# Sheet1.net
KiCad netlist of a schematic drawn in Altium Designer
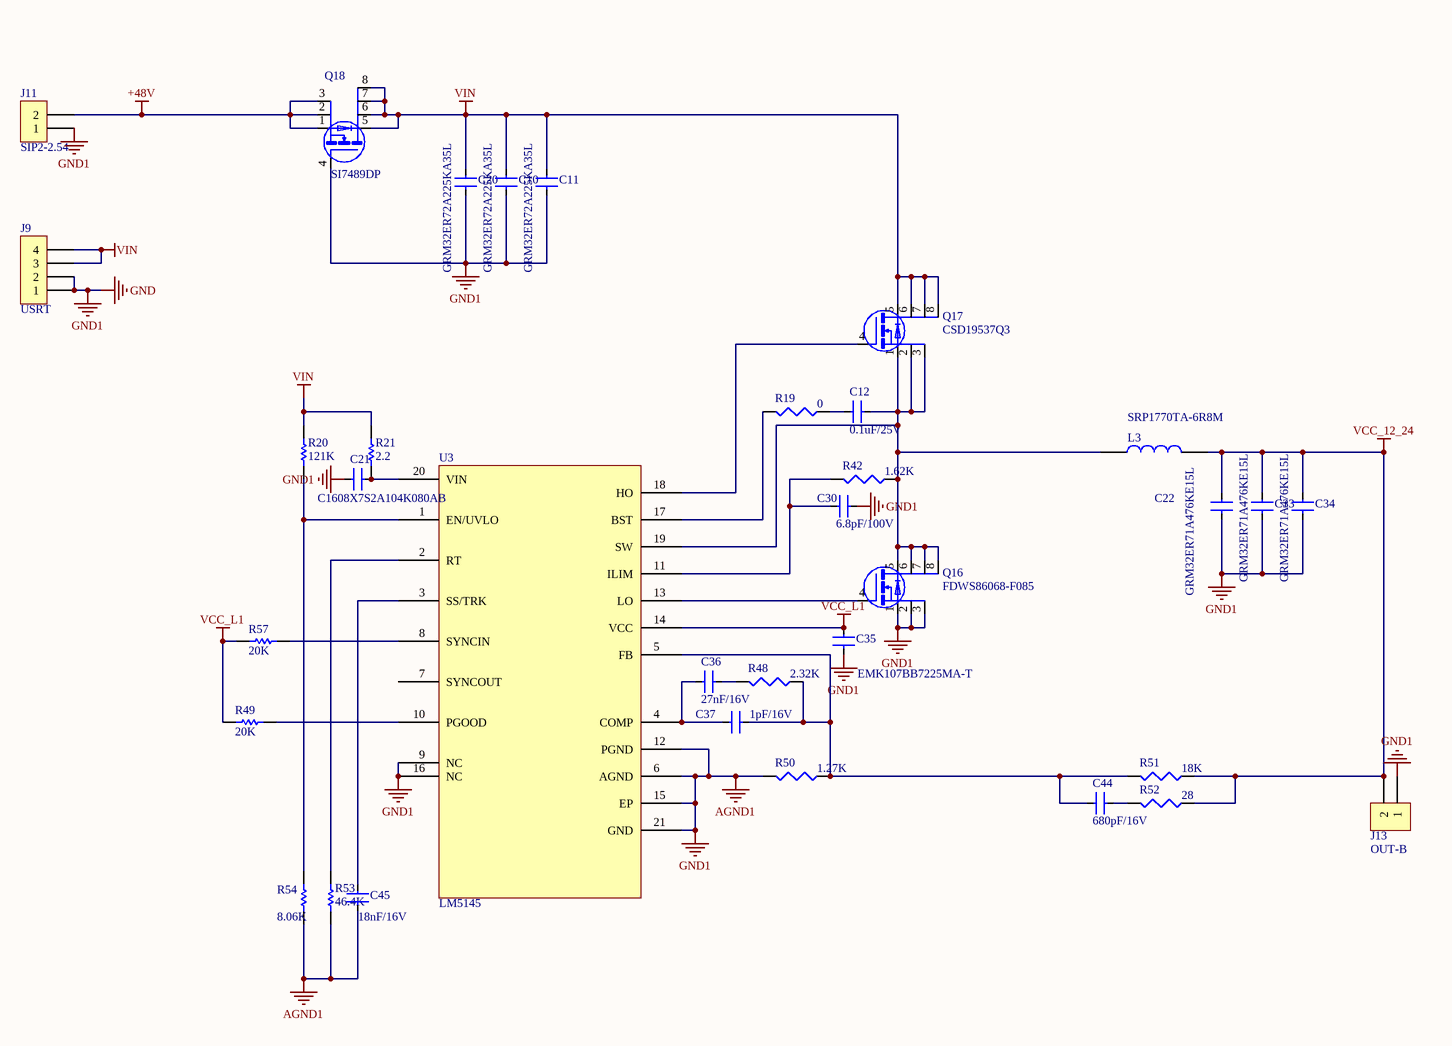
[diagram p0: Sheet1.SchDoc]

(export (version "E")
  (design (tool "Eeschema 10.0.6"))
  (components
    (comp (ref "C10")
      (value "GRM32ER72A225KA35L")
      (footprint "1210C")
      (description "CCX85-103")
      (libsource (lib "无极性电容") (part "0.01UF"))
    )
    (comp (ref "C11")
      (value "GRM32ER72A225KA35L")
      (footprint "1210C")
      (description "CCX85-103")
      (libsource (lib "无极性电容") (part "0.01UF"))
    )
    (comp (ref "C12")
      (value "0.1uF/25V")
      (footprint "0603C")
      (description "CCX85-103")
      (libsource (lib "无极性电容") (part "0.01UF"))
    )
    (comp (ref "C20")
      (value "GRM32ER72A225KA35L")
      (footprint "1210C")
      (description "CCX85-103")
      (libsource (lib "无极性电容") (part "0.01UF"))
    )
    (comp (ref "C21")
      (value "C1608X7S2A104K080AB")
      (footprint "0603C")
      (description "CCX85-103")
      (libsource (lib "无极性电容") (part "0.01UF"))
    )
    (comp (ref "C22")
      (value "GRM32ER71A476KE15L")
      (footprint "1210C")
      (description "CCX85-103")
      (libsource (lib "无极性电容") (part "0.01UF"))
    )
    (comp (ref "C30")
      (value "6.8pF/100V")
      (footprint "0603C")
      (description "CCX85-103")
      (libsource (lib "无极性电容") (part "0.01UF"))
    )
    (comp (ref "C33")
      (value "GRM32ER71A476KE15L")
      (footprint "1210C")
      (description "CCX85-103")
      (libsource (lib "无极性电容") (part "0.01UF"))
    )
    (comp (ref "C34")
      (value "GRM32ER71A476KE15L")
      (footprint "1210C")
      (description "CCX85-103")
      (libsource (lib "无极性电容") (part "0.01UF"))
    )
    (comp (ref "C35")
      (value "EMK107BB7225MA-T")
      (footprint "0603C")
      (description "CCX85-103")
      (libsource (lib "无极性电容") (part "0.01UF"))
    )
    (comp (ref "C36")
      (value "27nF/16V")
      (footprint "0603C")
      (description "CCX85-103")
      (libsource (lib "无极性电容") (part "0.01UF"))
    )
    (comp (ref "C37")
      (value "1pF/16V")
      (footprint "0603C")
      (description "CCX85-103")
      (libsource (lib "无极性电容") (part "0.01UF"))
    )
    (comp (ref "C44")
      (value "680pF/16V")
      (footprint "0603C")
      (description "CCX85-103")
      (libsource (lib "无极性电容") (part "0.01UF"))
    )
    (comp (ref "C45")
      (value "18nF/16V")
      (footprint "0603C")
      (description "CCX85-103")
      (libsource (lib "无极性电容") (part "0.01UF"))
    )
    (comp (ref "J9")
      (value "USRT")
      (footprint "SIP-4L")
      (description "CN-SIP4-2.54")
      (libsource (lib "接插件") (part "SIP4-2.54"))
    )
    (comp (ref "J11")
      (value "SIP2-2.54")
      (footprint "CH3.96-2P")
      (description "CN-SIP2-2.54")
      (libsource (lib "接插件") (part "SIP2-2.54"))
    )
    (comp (ref "J13")
      (value "OUT-B")
      (footprint "CH3.96-2P")
      (description "Connector")
      (libsource (lib "SM") (part "CON2"))
    )
    (comp (ref "L3")
      (value "SRP1770TA-6R8M")
      (footprint "SRP1270-2R2M")
      (libsource (lib "*") (part "INDUCTOR"))
    )
    (comp (ref "Q16")
      (value "FDWS86068-F085")
      (footprint "PowerPAK SO-8")
      (description "Si4004DY")
      (libsource (lib "Schlib_20110825") (part "Si4004DY"))
    )
    (comp (ref "Q17")
      (value "CSD19537Q3")
      (footprint "PowerPAK SO-8")
      (description "Si4004DY")
      (libsource (lib "Schlib_20110825") (part "Si4004DY"))
    )
    (comp (ref "Q18")
      (value "SI7489DP")
      (footprint "PowerPAK SO-8")
      (description "Si4004DY")
      (libsource (lib "") (part "Si4004DY_1"))
    )
    (comp (ref "R19")
      (value "0")
      (footprint "0603R")
      (description "Resistor")
      (fields (field (name "PUBLISHER") "Altium Limited"))
      (libsource (lib "SM") (part "Res3"))
    )
    (comp (ref "R20")
      (value "121K")
      (footprint "0805R")
      (description "Semiconductor Resistor")
      (fields (field (name "PUBLISHER") "Altium Limited"))
      (libsource (lib "Miscellaneous Devices") (part "Res Semi"))
    )
    (comp (ref "R21")
      (value "2.2")
      (footprint "0603R")
      (description "Semiconductor Resistor")
      (fields (field (name "PUBLISHER") "Altium Limited"))
      (libsource (lib "Miscellaneous Devices") (part "Res Semi"))
    )
    (comp (ref "R42")
      (value "1.62K")
      (footprint "0603R")
      (description "Resistor")
      (fields (field (name "PUBLISHER") "Altium Limited"))
      (libsource (lib "SM") (part "Res3"))
    )
    (comp (ref "R48")
      (value "2.32K")
      (footprint "0603R")
      (description "Resistor")
      (fields (field (name "PUBLISHER") "Altium Limited"))
      (libsource (lib "SM") (part "Res3"))
    )
    (comp (ref "R49")
      (value "20K")
      (footprint "0603R")
      (description "Semiconductor Resistor")
      (fields (field (name "PUBLISHER") "Altium Limited"))
      (libsource (lib "Miscellaneous Devices") (part "Res Semi"))
    )
    (comp (ref "R50")
      (value "1.27K")
      (footprint "0603R")
      (description "Resistor")
      (fields (field (name "PUBLISHER") "Altium Limited"))
      (libsource (lib "SM") (part "Res3"))
    )
    (comp (ref "R51")
      (value "18K")
      (footprint "0603R")
      (description "Resistor")
      (fields (field (name "PUBLISHER") "Altium Limited"))
      (libsource (lib "SM") (part "Res3"))
    )
    (comp (ref "R52")
      (value "28")
      (footprint "0603R")
      (description "Resistor")
      (fields (field (name "PUBLISHER") "Altium Limited"))
      (libsource (lib "SM") (part "Res3"))
    )
    (comp (ref "R53")
      (value "46.4K")
      (footprint "0603R")
      (description "Semiconductor Resistor")
      (fields (field (name "PUBLISHER") "Altium Limited"))
      (libsource (lib "Miscellaneous Devices") (part "Res Semi"))
    )
    (comp (ref "R54")
      (value "8.06K")
      (footprint "0603R")
      (description "Semiconductor Resistor")
      (fields (field (name "PUBLISHER") "Altium Limited"))
      (libsource (lib "Miscellaneous Devices") (part "Res Semi"))
    )
    (comp (ref "R57")
      (value "20K")
      (footprint "0603R")
      (description "Semiconductor Resistor")
      (fields (field (name "PUBLISHER") "Altium Limited"))
      (libsource (lib "Miscellaneous Devices") (part "Res Semi"))
    )
    (comp (ref "U3")
      (value "LM5145")
      (footprint "QFN050P600-8N")
      (libsource (lib "Schlib_20110825") (part "LM5145"))
    )
  )
  (nets
    (net (code "1") (name "+48V") (class "Default")
      (node (ref "J11") (pin "2") (pinfunction "2_2") (pintype "passive"))
      (node (ref "Q18") (pin "1") (pinfunction "S_1") (pintype "passive"))
      (node (ref "Q18") (pin "2") (pinfunction "S_2") (pintype "passive"))
      (node (ref "Q18") (pin "3") (pinfunction "S_3") (pintype "passive"))
    )
    (net (code "2") (name "AGND1") (class "Default")
      (node (ref "C10") (pin "2") (pinfunction "2_2") (pintype "passive"))
      (node (ref "C11") (pin "2") (pinfunction "2_2") (pintype "passive"))
      (node (ref "C20") (pin "2") (pinfunction "2_2") (pintype "passive"))
      (node (ref "C21") (pin "1") (pinfunction "1_1") (pintype "passive"))
      (node (ref "C22") (pin "2") (pinfunction "2_2") (pintype "passive"))
      (node (ref "C30") (pin "1") (pinfunction "1_1") (pintype "passive"))
      (node (ref "C33") (pin "2") (pinfunction "2_2") (pintype "passive"))
      (node (ref "C34") (pin "2") (pinfunction "2_2") (pintype "passive"))
      (node (ref "C35") (pin "2") (pinfunction "2_2") (pintype "passive"))
      (node (ref "C45") (pin "2") (pinfunction "2_2") (pintype "passive"))
      (node (ref "J11") (pin "1") (pinfunction "1_1") (pintype "passive"))
      (node (ref "J13") (pin "1") (pinfunction "1_1") (pintype "passive"))
      (node (ref "J9") (pin "1") (pinfunction "1_1") (pintype "passive"))
      (node (ref "J9") (pin "2") (pinfunction "2_2") (pintype "passive"))
      (node (ref "Q16") (pin "1") (pinfunction "S_1") (pintype "passive"))
      (node (ref "Q16") (pin "2") (pinfunction "S_2") (pintype "passive"))
      (node (ref "Q16") (pin "3") (pinfunction "S_3") (pintype "passive"))
      (node (ref "Q18") (pin "4") (pinfunction "G_4") (pintype "passive"))
      (node (ref "R50") (pin "2") (pinfunction "2_2") (pintype "passive"))
      (node (ref "R53") (pin "1") (pinfunction "1_1") (pintype "passive"))
      (node (ref "R54") (pin "1") (pinfunction "1_1") (pintype "passive"))
      (node (ref "U3") (pin "12") (pinfunction "PGND_12") (pintype "passive"))
      (node (ref "U3") (pin "15") (pinfunction "EP_15") (pintype "passive"))
      (node (ref "U3") (pin "16") (pinfunction "NC_16") (pintype "passive"))
      (node (ref "U3") (pin "21") (pinfunction "GND_21") (pintype "passive"))
      (node (ref "U3") (pin "6") (pinfunction "AGND_6") (pintype "passive"))
      (node (ref "U3") (pin "9") (pinfunction "NC_9") (pintype "passive"))
    )
    (net (code "3") (name "Net-(C12-Pad1)") (class "Default")
      (node (ref "C12") (pin "1") (pinfunction "1_1") (pintype "passive"))
      (node (ref "R19") (pin "1") (pinfunction "1_1") (pintype "passive"))
    )
    (net (code "4") (name "Net-(C36-Pad2)") (class "Default")
      (node (ref "C36") (pin "2") (pinfunction "2_2") (pintype "passive"))
      (node (ref "R48") (pin "2") (pinfunction "2_2") (pintype "passive"))
    )
    (net (code "5") (name "Net-(C44-Pad2)") (class "Default")
      (node (ref "C44") (pin "2") (pinfunction "2_2") (pintype "passive"))
      (node (ref "R52") (pin "2") (pinfunction "2_2") (pintype "passive"))
    )
    (net (code "6") (name "Net-(Q16-G)") (class "Default")
      (node (ref "Q16") (pin "4") (pinfunction "G_4") (pintype "passive"))
      (node (ref "U3") (pin "13") (pinfunction "LO_13") (pintype "passive"))
    )
    (net (code "7") (name "Net-(Q17-G)") (class "Default")
      (node (ref "Q17") (pin "4") (pinfunction "G_4") (pintype "passive"))
      (node (ref "U3") (pin "18") (pinfunction "HO_18") (pintype "passive"))
    )
    (net (code "8") (name "Net-(U3-BST)") (class "Default")
      (node (ref "R19") (pin "2") (pinfunction "2_2") (pintype "passive"))
      (node (ref "U3") (pin "17") (pinfunction "BST_17") (pintype "passive"))
    )
    (net (code "9") (name "Net-(U3-COMP)") (class "Default")
      (node (ref "C36") (pin "1") (pinfunction "1_1") (pintype "passive"))
      (node (ref "C37") (pin "1") (pinfunction "1_1") (pintype "passive"))
      (node (ref "U3") (pin "4") (pinfunction "COMP_4") (pintype "passive"))
    )
    (net (code "10") (name "Net-(U3-EN{slash}UVLO)") (class "Default")
      (node (ref "R20") (pin "1") (pinfunction "1_1") (pintype "passive"))
      (node (ref "R54") (pin "2") (pinfunction "2_2") (pintype "passive"))
      (node (ref "U3") (pin "1") (pinfunction "EN/UVLO_1") (pintype "passive"))
    )
    (net (code "11") (name "Net-(U3-FB)") (class "Default")
      (node (ref "C37") (pin "2") (pinfunction "2_2") (pintype "passive"))
      (node (ref "C44") (pin "1") (pinfunction "1_1") (pintype "passive"))
      (node (ref "R48") (pin "1") (pinfunction "1_1") (pintype "passive"))
      (node (ref "R50") (pin "1") (pinfunction "1_1") (pintype "passive"))
      (node (ref "R51") (pin "2") (pinfunction "2_2") (pintype "passive"))
      (node (ref "U3") (pin "5") (pinfunction "FB_5") (pintype "passive"))
    )
    (net (code "12") (name "Net-(U3-ILIM)") (class "Default")
      (node (ref "C30") (pin "2") (pinfunction "2_2") (pintype "passive"))
      (node (ref "R42") (pin "2") (pinfunction "2_2") (pintype "passive"))
      (node (ref "U3") (pin "11") (pinfunction "ILIM_11") (pintype "passive"))
    )
    (net (code "13") (name "Net-(U3-PGOOD)") (class "Default")
      (node (ref "R49") (pin "1") (pinfunction "1_1") (pintype "passive"))
      (node (ref "U3") (pin "10") (pinfunction "PGOOD_10") (pintype "passive"))
    )
    (net (code "14") (name "Net-(U3-RT)") (class "Default")
      (node (ref "R53") (pin "2") (pinfunction "2_2") (pintype "passive"))
      (node (ref "U3") (pin "2") (pinfunction "RT_2") (pintype "passive"))
    )
    (net (code "15") (name "Net-(U3-SS{slash}TRK)") (class "Default")
      (node (ref "C45") (pin "1") (pinfunction "1_1") (pintype "passive"))
      (node (ref "U3") (pin "3") (pinfunction "SS/TRK_3") (pintype "passive"))
    )
    (net (code "16") (name "Net-(U3-SW)") (class "Default")
      (node (ref "C12") (pin "2") (pinfunction "2_2") (pintype "passive"))
      (node (ref "L3") (pin "1") (pinfunction "1_1") (pintype "passive"))
      (node (ref "Q16") (pin "5") (pinfunction "D_5") (pintype "passive"))
      (node (ref "Q16") (pin "6") (pinfunction "D_6") (pintype "passive"))
      (node (ref "Q16") (pin "7") (pinfunction "D_7") (pintype "passive"))
      (node (ref "Q16") (pin "8") (pinfunction "D_8") (pintype "passive"))
      (node (ref "Q17") (pin "1") (pinfunction "S_1") (pintype "passive"))
      (node (ref "Q17") (pin "2") (pinfunction "S_2") (pintype "passive"))
      (node (ref "Q17") (pin "3") (pinfunction "S_3") (pintype "passive"))
      (node (ref "R42") (pin "1") (pinfunction "1_1") (pintype "passive"))
      (node (ref "U3") (pin "19") (pinfunction "SW_19") (pintype "passive"))
    )
    (net (code "17") (name "Net-(U3-SYNCIN)") (class "Default")
      (node (ref "R57") (pin "1") (pinfunction "1_1") (pintype "passive"))
      (node (ref "U3") (pin "8") (pinfunction "SYNCIN_8") (pintype "passive"))
    )
    (net (code "18") (name "Net-(U3-VIN)") (class "Default")
      (node (ref "C21") (pin "2") (pinfunction "2_2") (pintype "passive"))
      (node (ref "R21") (pin "2") (pinfunction "2_2") (pintype "passive"))
      (node (ref "U3") (pin "20") (pinfunction "VIN_20") (pintype "passive"))
    )
    (net (code "19") (name "VCC_12_24") (class "Default")
      (node (ref "C22") (pin "1") (pinfunction "1_1") (pintype "passive"))
      (node (ref "C33") (pin "1") (pinfunction "1_1") (pintype "passive"))
      (node (ref "C34") (pin "1") (pinfunction "1_1") (pintype "passive"))
      (node (ref "J13") (pin "2") (pinfunction "2_2") (pintype "passive"))
      (node (ref "L3") (pin "2") (pinfunction "2_2") (pintype "passive"))
      (node (ref "R51") (pin "1") (pinfunction "1_1") (pintype "passive"))
      (node (ref "R52") (pin "1") (pinfunction "1_1") (pintype "passive"))
    )
    (net (code "20") (name "VCC_L1") (class "Default")
      (node (ref "C35") (pin "1") (pinfunction "1_1") (pintype "passive"))
      (node (ref "R49") (pin "2") (pinfunction "2_2") (pintype "passive"))
      (node (ref "R57") (pin "2") (pinfunction "2_2") (pintype "passive"))
      (node (ref "U3") (pin "14") (pinfunction "VCC_14") (pintype "passive"))
    )
    (net (code "21") (name "VIN") (class "Default")
      (node (ref "C10") (pin "1") (pinfunction "1_1") (pintype "passive"))
      (node (ref "C11") (pin "1") (pinfunction "1_1") (pintype "passive"))
      (node (ref "C20") (pin "1") (pinfunction "1_1") (pintype "passive"))
      (node (ref "J9") (pin "3") (pinfunction "3_3") (pintype "passive"))
      (node (ref "J9") (pin "4") (pinfunction "4_4") (pintype "passive"))
      (node (ref "Q17") (pin "5") (pinfunction "D_5") (pintype "passive"))
      (node (ref "Q17") (pin "6") (pinfunction "D_6") (pintype "passive"))
      (node (ref "Q17") (pin "7") (pinfunction "D_7") (pintype "passive"))
      (node (ref "Q17") (pin "8") (pinfunction "D_8") (pintype "passive"))
      (node (ref "Q18") (pin "5") (pinfunction "D_5") (pintype "passive"))
      (node (ref "Q18") (pin "6") (pinfunction "D_6") (pintype "passive"))
      (node (ref "Q18") (pin "7") (pinfunction "D_7") (pintype "passive"))
      (node (ref "Q18") (pin "8") (pinfunction "D_8") (pintype "passive"))
      (node (ref "R20") (pin "2") (pinfunction "2_2") (pintype "passive"))
      (node (ref "R21") (pin "1") (pinfunction "1_1") (pintype "passive"))
    )
    (net (code "22") (name "unconnected-(U3-SYNCOUT-Pad7)") (class "Default")
      (node (ref "U3") (pin "7") (pinfunction "SYNCOUT_7") (pintype "passive"))
    )
  )
)
